# Croduino_SAMD_v1_0.net
KiCad netlist of a schematic drawn in EAGLE
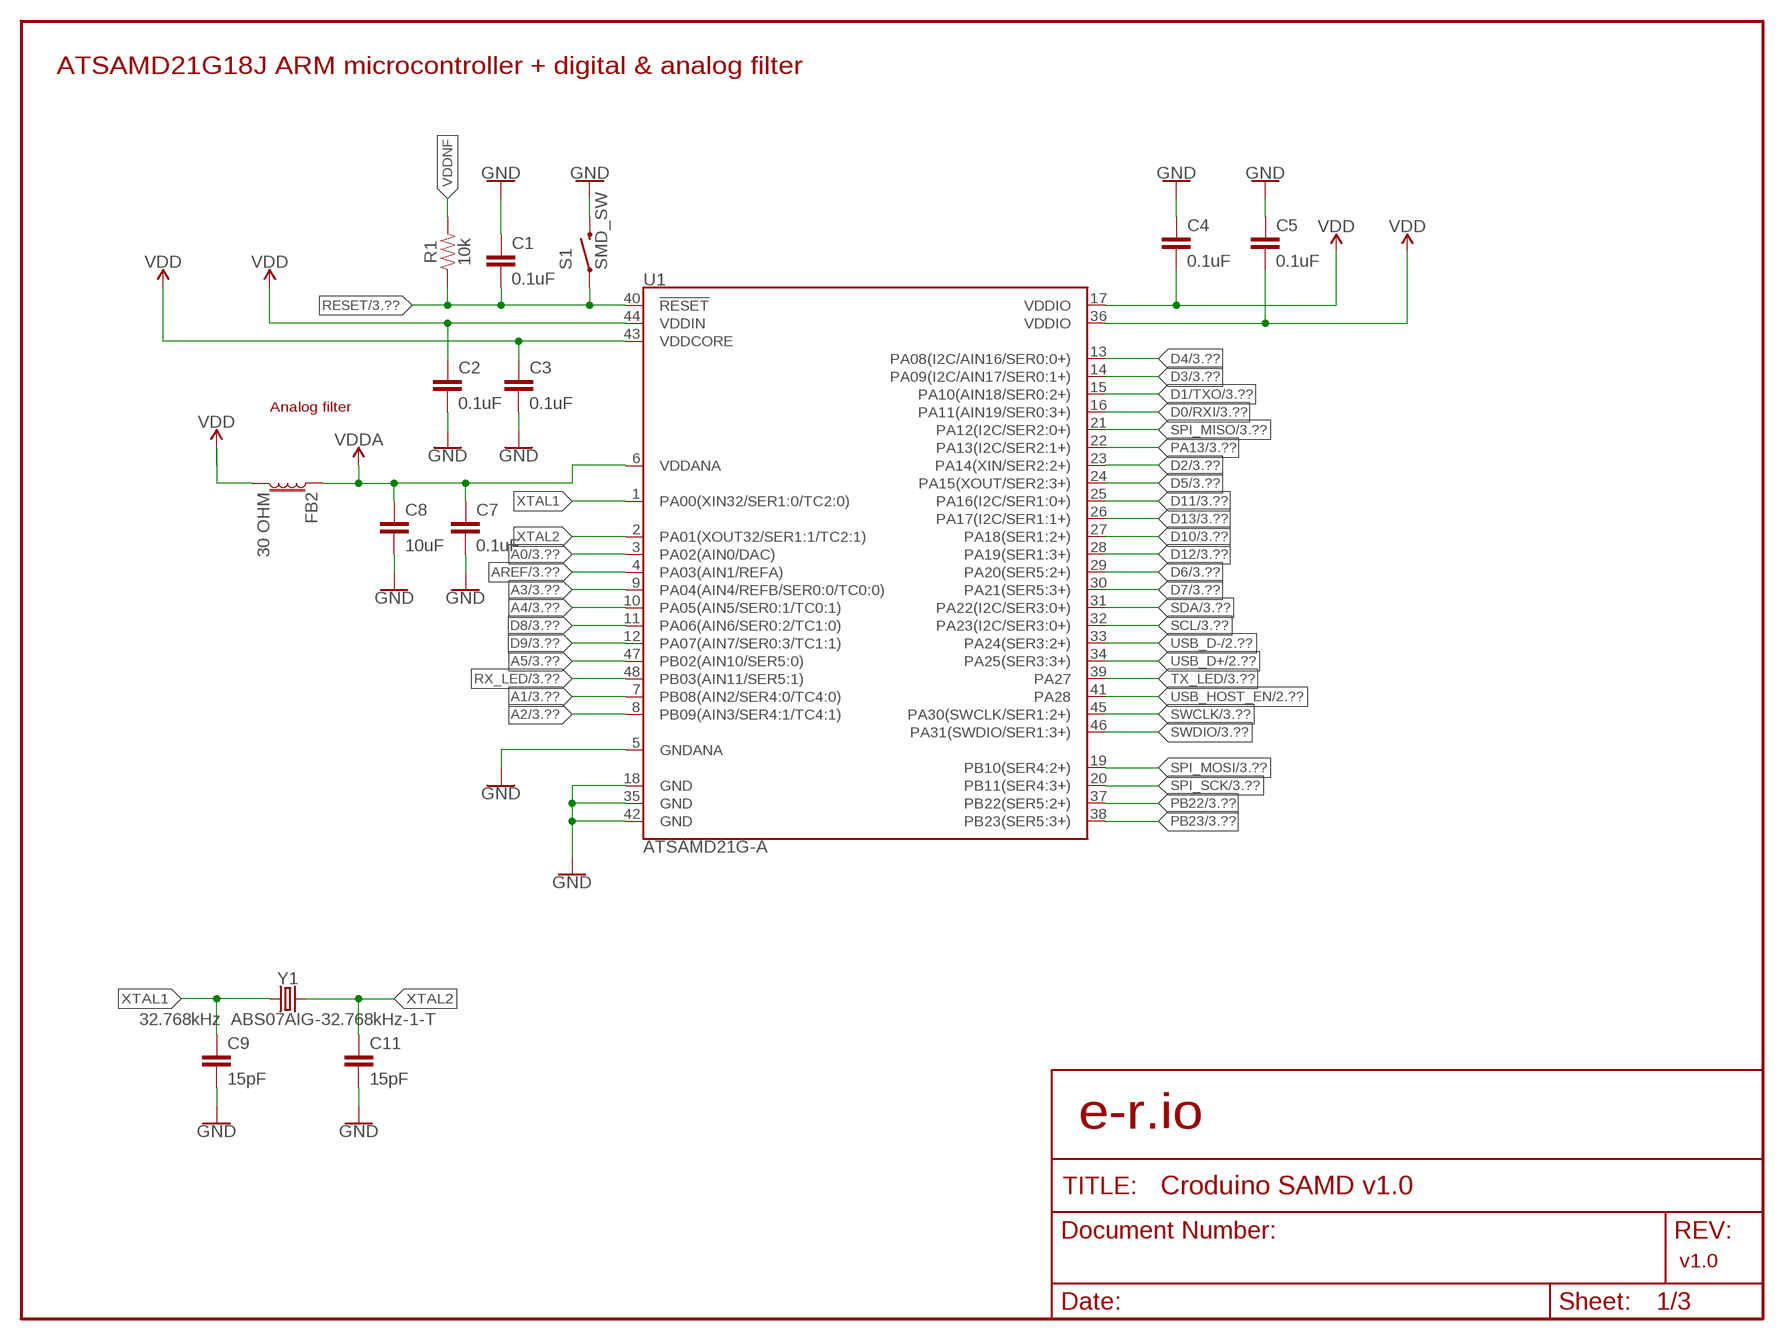
[diagram p0: schematic, sheet 1]
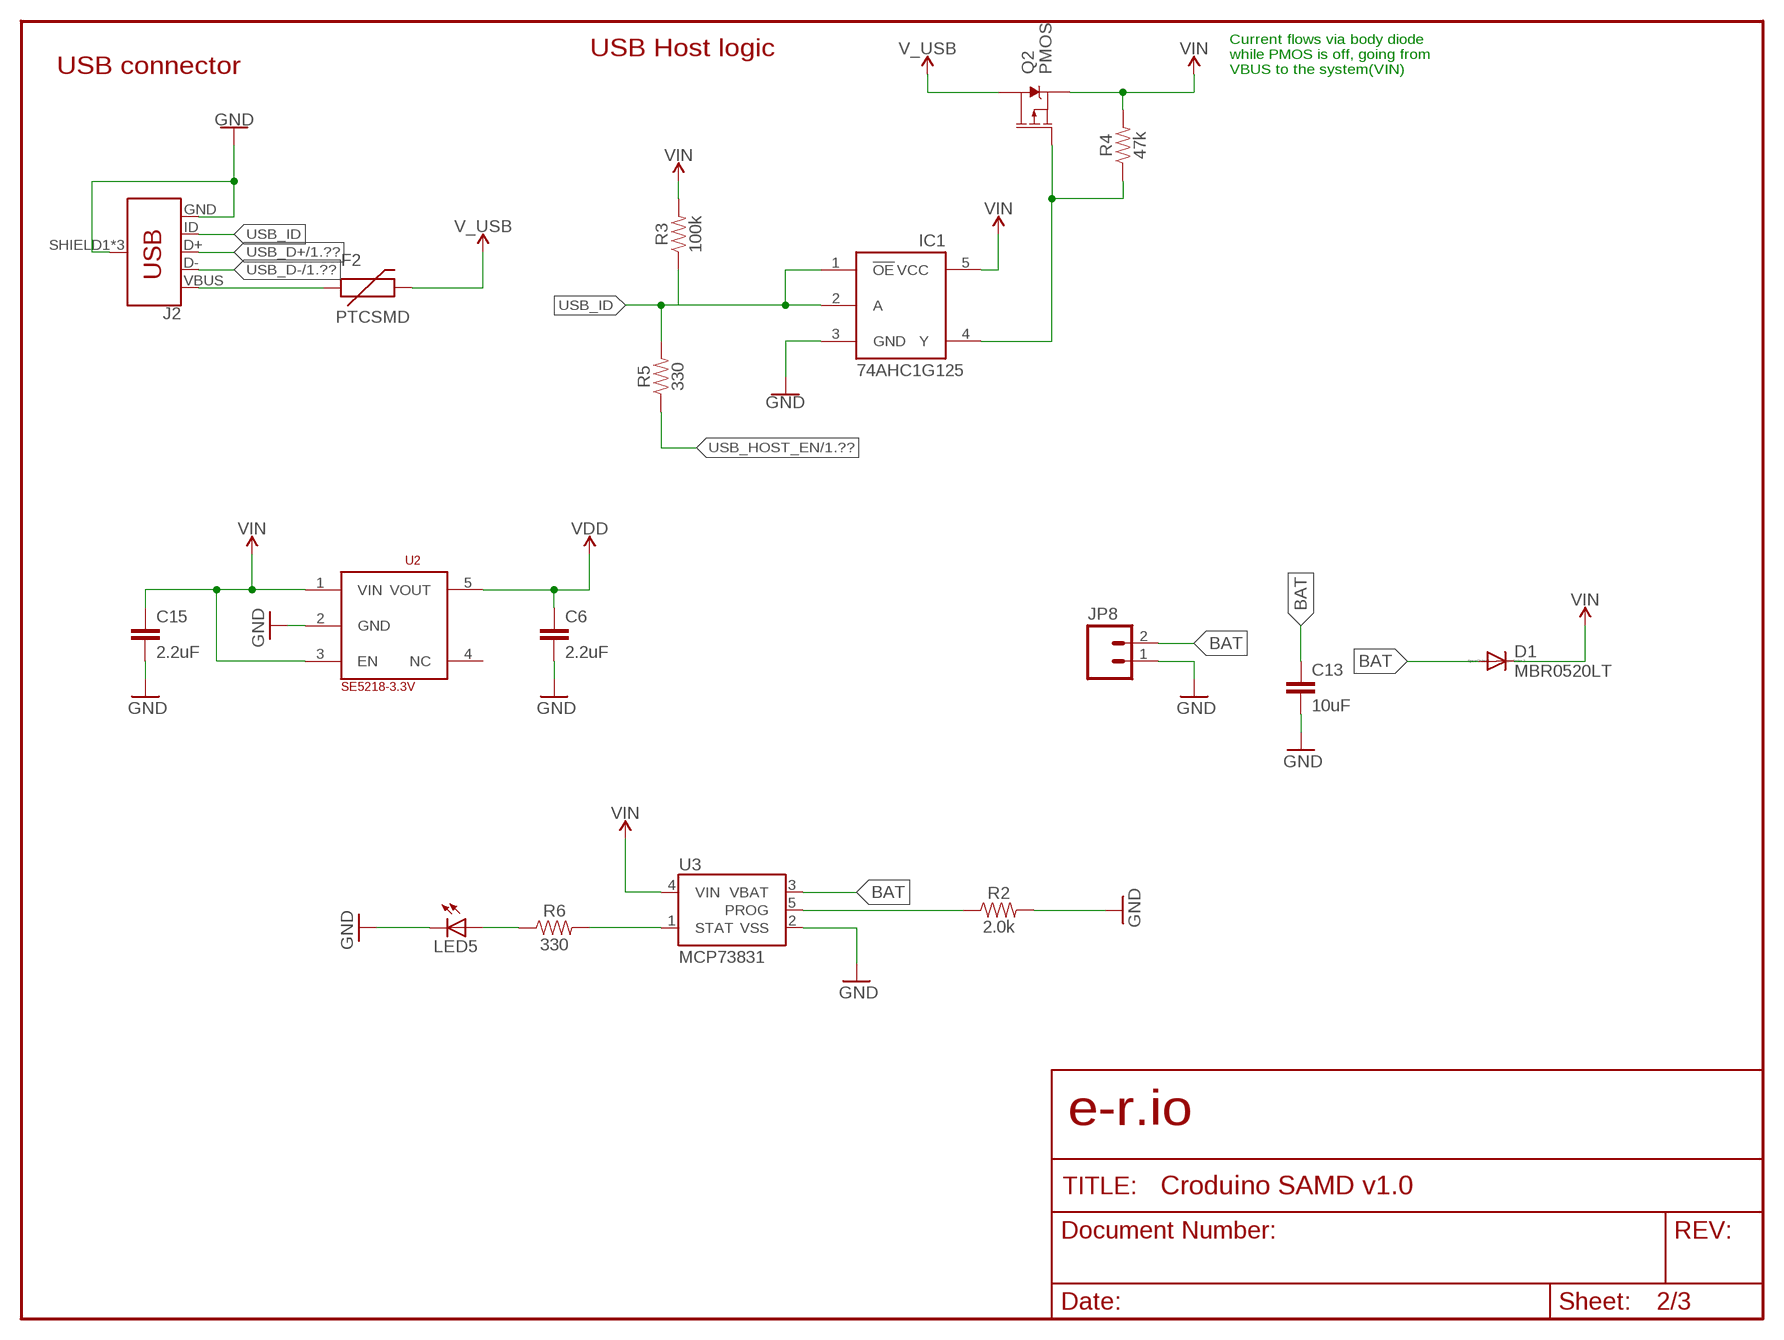
[diagram p1: schematic, sheet 2]
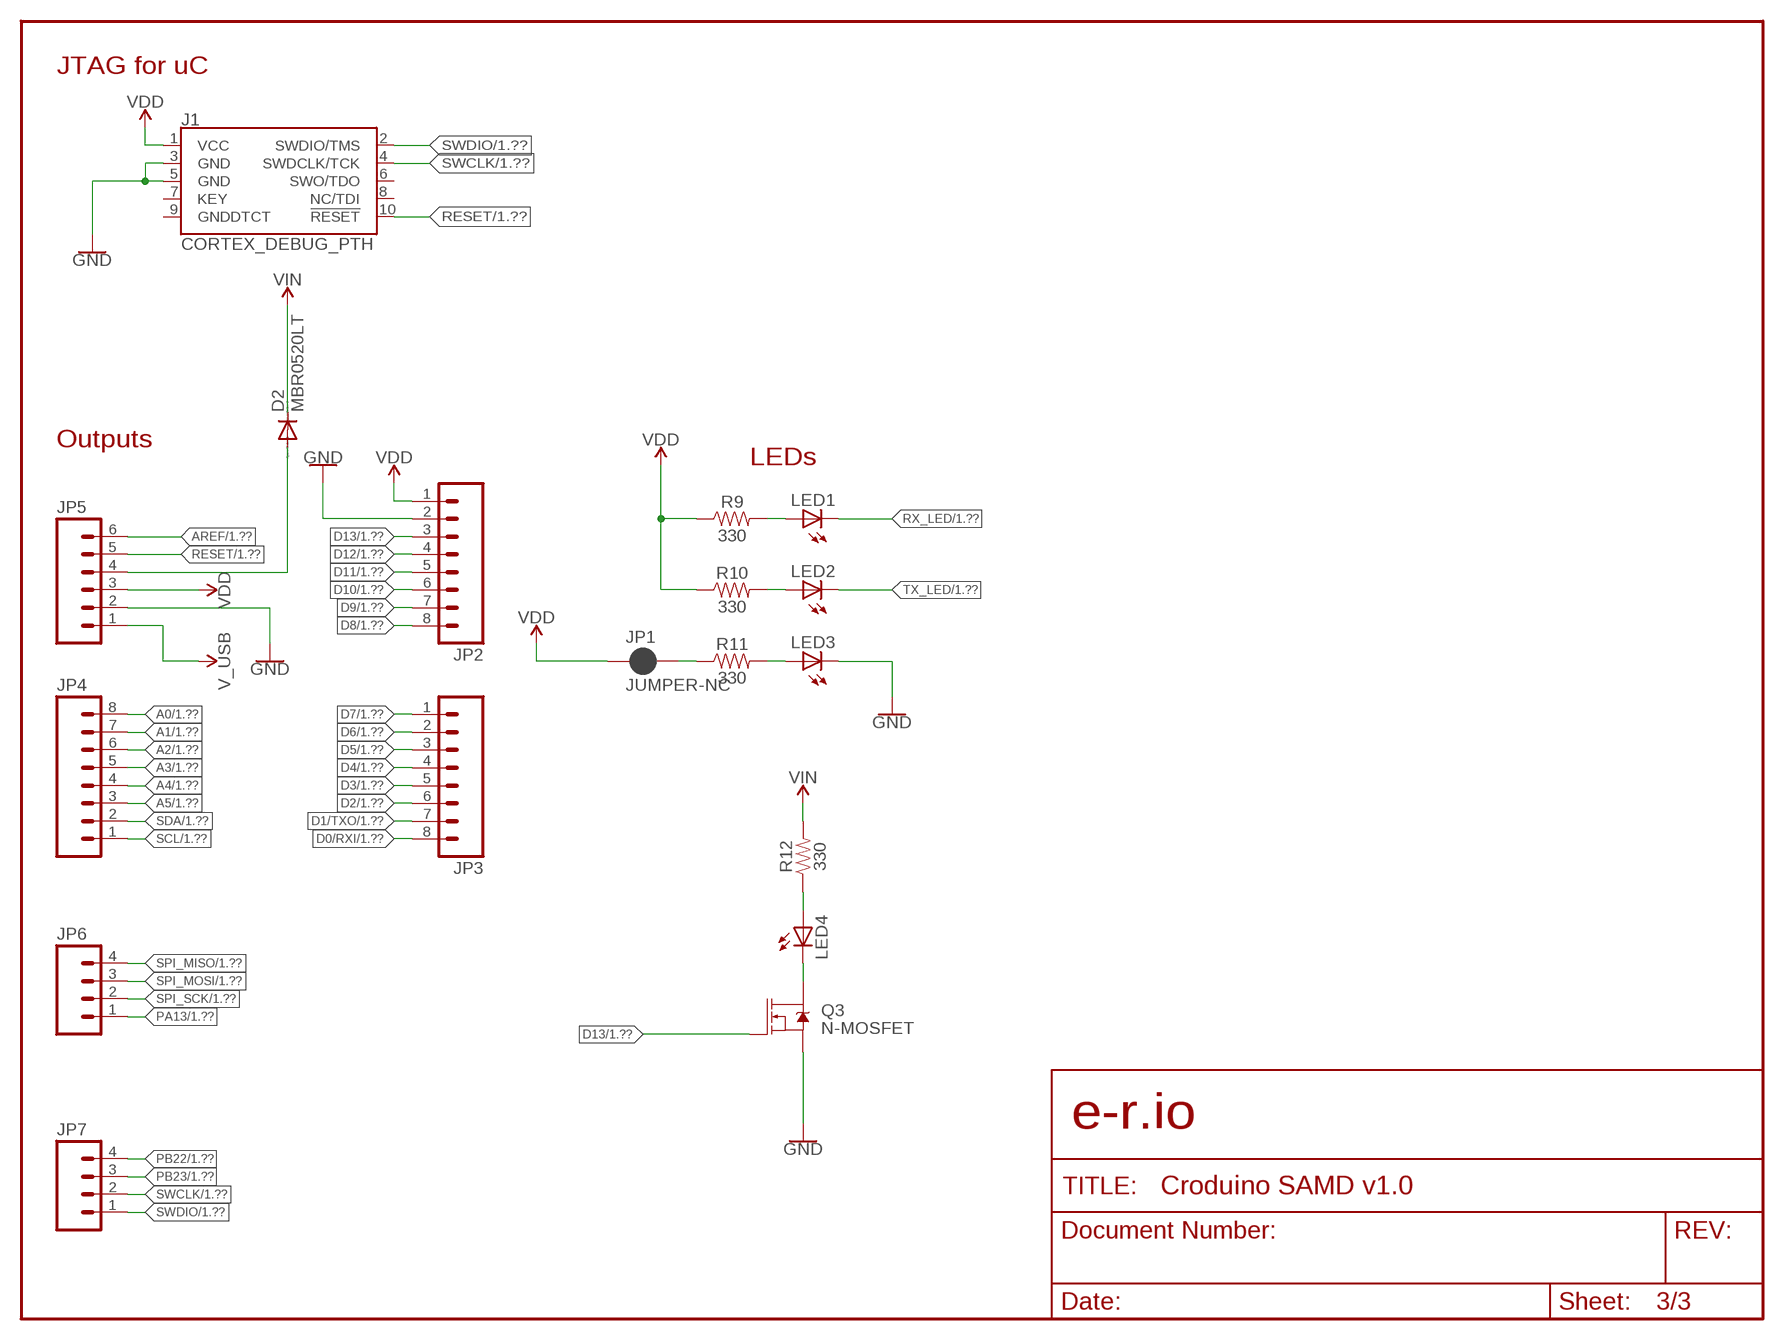
[diagram p2: schematic, sheet 3]

(export (version "E")
  (design (tool "Eeschema 10.0.6"))
  (components
    (comp (ref "C6")
      (value "2.2uF")
      (footprint "eagle-import:0603")
      (libsource (lib "eagle-import") (part "2.2UF-0603-10V-20%"))
    )
    (comp (ref "C13")
      (value "10uF")
      (footprint "eagle-import:1206")
      (libsource (lib "eagle-import") (part "10UF-1206-6.3V-20%"))
    )
    (comp (ref "C15")
      (value "2.2uF")
      (footprint "eagle-import:0603")
      (libsource (lib "eagle-import") (part "2.2UF-0603-10V-20%"))
    )
    (comp (ref "D1")
      (value "MBR0520LT")
      (footprint "eagle-import:SOD123")
      (libsource (lib "eagle-import") (part "MBR0520LT"))
    )
    (comp (ref "F2")
      (value "PTCSMD")
      (footprint "eagle-import:PTC-1206")
      (libsource (lib "eagle-import") (part "PTCSMD"))
    )
    (comp (ref "IC1")
      (value "74AHC1G125")
      (footprint "eagle-import:SOT23-5L")
      (libsource (lib "eagle-import") (part "74AHC1G125"))
    )
    (comp (ref "J2")
      (value "USB_MICRO-BREDUCED_PASTE")
      (footprint "eagle-import:USB-B-MICRO-SMD_RED_PASTE")
      (libsource (lib "eagle-import") (part "USB_MICRO-BREDUCED_PASTE"))
    )
    (comp (ref "JP8")
      (value "M02-JST-2MM-SMT")
      (footprint "eagle-import:JST-2-SMD")
      (libsource (lib "eagle-import") (part "M02-JST-2MM-SMT"))
    )
    (comp (ref "LED5")
      (value "LEDCHIPLED_0805")
      (footprint "eagle-import:CHIPLED_0805")
      (libsource (lib "eagle-import") (part "LEDCHIPLED_0805"))
    )
    (comp (ref "Q2")
      (value "PMOS")
      (footprint "eagle-import:SOT23-3")
      (libsource (lib "eagle-import") (part "MOSFET_PCH-DMG2307L"))
    )
    (comp (ref "R2")
      (value "2.0k")
      (footprint "eagle-import:0603")
      (libsource (lib "eagle-import") (part "2.0KOHM-0603-1/10W-5%"))
    )
    (comp (ref "R3")
      (value "100k")
      (footprint "eagle-import:0603")
      (libsource (lib "eagle-import") (part "100KOHM-0603-1/10W-1%"))
    )
    (comp (ref "R4")
      (value "47k")
      (footprint "eagle-import:0603")
      (libsource (lib "eagle-import") (part "47KOHM-0603-1/10W-1%"))
    )
    (comp (ref "R5")
      (value "330")
      (footprint "eagle-import:0603")
      (libsource (lib "eagle-import") (part "330OHM-0603-1/10W-1%"))
    )
    (comp (ref "R6")
      (value "330")
      (footprint "eagle-import:0603")
      (libsource (lib "eagle-import") (part "330OHM-0603-1/10W-1%"))
    )
    (comp (ref "U2")
      (value "SE5218-3.3V")
      (footprint "eagle-import:SOT23-5")
      (libsource (lib "eagle-import") (part "SE5218"))
    )
    (comp (ref "U3")
      (value "MCP73831")
      (footprint "eagle-import:SOT23-5")
      (libsource (lib "eagle-import") (part "MCP73831"))
    )
    (comp (ref "C1")
      (value "0.1uF")
      (footprint "eagle-import:0603")
      (libsource (lib "eagle-import") (part "0.1UF-0603-25V-(+80/-20%)"))
    )
    (comp (ref "C2")
      (value "0.1uF")
      (footprint "eagle-import:0603")
      (libsource (lib "eagle-import") (part "0.1UF-0603-25V-(+80/-20%)"))
    )
    (comp (ref "C3")
      (value "0.1uF")
      (footprint "eagle-import:0603")
      (libsource (lib "eagle-import") (part "0.1UF-0603-25V-(+80/-20%)"))
    )
    (comp (ref "C4")
      (value "0.1uF")
      (footprint "eagle-import:0603")
      (libsource (lib "eagle-import") (part "0.1UF-0603-25V-(+80/-20%)"))
    )
    (comp (ref "C5")
      (value "0.1uF")
      (footprint "eagle-import:0603")
      (libsource (lib "eagle-import") (part "0.1UF-0603-25V-(+80/-20%)"))
    )
    (comp (ref "C7")
      (value "0.1uF")
      (footprint "eagle-import:0603")
      (libsource (lib "eagle-import") (part "0.1UF-0603-25V-(+80/-20%)"))
    )
    (comp (ref "C8")
      (value "10uF")
      (footprint "eagle-import:1206")
      (libsource (lib "eagle-import") (part "10UF-1206-6.3V-20%"))
    )
    (comp (ref "C9")
      (value "15pF")
      (footprint "eagle-import:0603")
      (libsource (lib "eagle-import") (part "15PF-0603-50V-5%"))
    )
    (comp (ref "C11")
      (value "15pF")
      (footprint "eagle-import:0603")
      (libsource (lib "eagle-import") (part "15PF-0603-50V-5%"))
    )
    (comp (ref "FB2")
      (value "30 OHM")
      (footprint "eagle-import:0603")
      (libsource (lib "eagle-import") (part "FERRITE_BEAD-0603"))
    )
    (comp (ref "R1")
      (value "10k")
      (footprint "eagle-import:0603")
      (libsource (lib "eagle-import") (part "10KOHM-0603-1/10W-1%"))
    )
    (comp (ref "S1")
      (value "SMD_SW")
      (footprint "eagle-import:TACTILE_SWITCH_SMD")
      (libsource (lib "eagle-import") (part "SWITCH-MOMENTARY-2SMD"))
    )
    (comp (ref "U1")
      (value "ATSAMD21G-A")
      (footprint "eagle-import:TQFP-48")
      (libsource (lib "eagle-import") (part "ATSAMD21G-A"))
    )
    (comp (ref "Y1")
      (value "32.768kHz ABS07AIG-32.768kHz-1-T")
      (footprint "eagle-import:CRYSTAL-SMD-3.2X1.5MM")
      (libsource (lib "eagle-import") (part "CRYSTAL-32.768KHZSMD-3.2X1.5"))
    )
    (comp (ref "D2")
      (value "MBR0520LT")
      (footprint "eagle-import:SOD123")
      (libsource (lib "eagle-import") (part "MBR0520LT"))
    )
    (comp (ref "J1")
      (value "CORTEX_DEBUG_PTH")
      (footprint "eagle-import:2X5-PTH-1.27MM")
      (libsource (lib "eagle-import") (part "CORTEX_DEBUG_PTH"))
    )
    (comp (ref "JP1")
      (value "JUMPER-NC")
      (footprint "eagle-import:SMT-JUMPER_2_NC_PASTE_NO-SILK")
      (libsource (lib "eagle-import") (part "JUMPER-SMT_2_NC_PASTE_NO-SILK"))
    )
    (comp (ref "JP2")
      (value "M081X08")
      (footprint "eagle-import:1X08")
      (libsource (lib "eagle-import") (part "M081X08"))
    )
    (comp (ref "JP3")
      (value "M081X08")
      (footprint "eagle-import:1X08")
      (libsource (lib "eagle-import") (part "M081X08"))
    )
    (comp (ref "JP4")
      (value "M081X08")
      (footprint "eagle-import:1X08")
      (libsource (lib "eagle-import") (part "M081X08"))
    )
    (comp (ref "JP5")
      (value "M06SIP")
      (footprint "eagle-import:1X06")
      (libsource (lib "eagle-import") (part "M06SIP"))
    )
    (comp (ref "JP6")
      (value "M04PTH")
      (footprint "eagle-import:1X04")
      (libsource (lib "eagle-import") (part "M04PTH"))
    )
    (comp (ref "JP7")
      (value "M04PTH")
      (footprint "eagle-import:1X04")
      (libsource (lib "eagle-import") (part "M04PTH"))
    )
    (comp (ref "LED1")
      (value "LEDCHIPLED_0805")
      (footprint "eagle-import:CHIPLED_0805")
      (libsource (lib "eagle-import") (part "LEDCHIPLED_0805"))
    )
    (comp (ref "LED2")
      (value "LEDCHIPLED_0805")
      (footprint "eagle-import:CHIPLED_0805")
      (libsource (lib "eagle-import") (part "LEDCHIPLED_0805"))
    )
    (comp (ref "LED3")
      (value "LEDCHIPLED_0805")
      (footprint "eagle-import:CHIPLED_0805")
      (libsource (lib "eagle-import") (part "LEDCHIPLED_0805"))
    )
    (comp (ref "LED4")
      (value "LEDCHIPLED_0805")
      (footprint "eagle-import:CHIPLED_0805")
      (libsource (lib "eagle-import") (part "LEDCHIPLED_0805"))
    )
    (comp (ref "Q3")
      (value "N-MOSFET")
      (footprint "eagle-import:SOT23-3")
      (libsource (lib "eagle-import") (part "MOSFET-NCH-AO3404A"))
    )
    (comp (ref "R9")
      (value "330")
      (footprint "eagle-import:0603")
      (libsource (lib "eagle-import") (part "330OHM-0603-1/10W-1%"))
    )
    (comp (ref "R10")
      (value "330")
      (footprint "eagle-import:0603")
      (libsource (lib "eagle-import") (part "330OHM-0603-1/10W-1%"))
    )
    (comp (ref "R11")
      (value "330")
      (footprint "eagle-import:0603")
      (libsource (lib "eagle-import") (part "330OHM-0603-1/10W-1%"))
    )
    (comp (ref "R12")
      (value "330")
      (footprint "eagle-import:0603")
      (libsource (lib "eagle-import") (part "330OHM-0603-1/10W-1%"))
    )
  )
  (nets
    (net (code "1") (name "A0") (class "Default")
      (node (ref "JP4") (pin "8") (pinfunction "8_8") (pintype "passive"))
      (node (ref "U1") (pin "3") (pinfunction "PA02(AIN0/DAC)_3") (pintype "bidirectional"))
    )
    (net (code "2") (name "A1") (class "Default")
      (node (ref "JP4") (pin "7") (pinfunction "7_7") (pintype "passive"))
      (node (ref "U1") (pin "7") (pinfunction "PB08(AIN2/SER4:0/TC4:0)_7") (pintype "bidirectional"))
    )
    (net (code "3") (name "A2") (class "Default")
      (node (ref "JP4") (pin "6") (pinfunction "6_6") (pintype "passive"))
      (node (ref "U1") (pin "8") (pinfunction "PB09(AIN3/SER4:1/TC4:1)_8") (pintype "bidirectional"))
    )
    (net (code "4") (name "A3") (class "Default")
      (node (ref "JP4") (pin "5") (pinfunction "5_5") (pintype "passive"))
      (node (ref "U1") (pin "9") (pinfunction "PA04(AIN4/REFB/SER0:0/TC0:0)_9") (pintype "bidirectional"))
    )
    (net (code "5") (name "A4") (class "Default")
      (node (ref "JP4") (pin "4") (pinfunction "4_4") (pintype "passive"))
      (node (ref "U1") (pin "10") (pinfunction "PA05(AIN5/SER0:1/TC0:1)_10") (pintype "bidirectional"))
    )
    (net (code "6") (name "A5") (class "Default")
      (node (ref "JP4") (pin "3") (pinfunction "3_3") (pintype "passive"))
      (node (ref "U1") (pin "47") (pinfunction "PB02(AIN10/SER5:0)_47") (pintype "bidirectional"))
    )
    (net (code "7") (name "AREF") (class "Default")
      (node (ref "JP5") (pin "6") (pinfunction "6_6") (pintype "passive"))
      (node (ref "U1") (pin "4") (pinfunction "PA03(AIN1/REFA)_4") (pintype "bidirectional"))
    )
    (net (code "8") (name "BAT") (class "Default")
      (node (ref "C13") (pin "1") (pinfunction "1_1") (pintype "passive"))
      (node (ref "D1") (pin "A") (pinfunction "A_A") (pintype "passive"))
      (node (ref "JP8") (pin "2") (pinfunction "2_2") (pintype "passive"))
      (node (ref "U3") (pin "3") (pinfunction "VBAT_3") (pintype "power_in"))
    )
    (net (code "9") (name "D0{slash}RXI") (class "Default")
      (node (ref "JP3") (pin "8") (pinfunction "8_8") (pintype "passive"))
      (node (ref "U1") (pin "16") (pinfunction "PA11(AIN19/SER0:3+)_16") (pintype "bidirectional"))
    )
    (net (code "10") (name "D1{slash}TXO") (class "Default")
      (node (ref "JP3") (pin "7") (pinfunction "7_7") (pintype "passive"))
      (node (ref "U1") (pin "15") (pinfunction "PA10(AIN18/SER0:2+)_15") (pintype "bidirectional"))
    )
    (net (code "11") (name "D2") (class "Default")
      (node (ref "JP3") (pin "6") (pinfunction "6_6") (pintype "passive"))
      (node (ref "U1") (pin "23") (pinfunction "PA14(XIN/SER2:2+)_23") (pintype "bidirectional"))
    )
    (net (code "12") (name "D3") (class "Default")
      (node (ref "JP3") (pin "5") (pinfunction "5_5") (pintype "passive"))
      (node (ref "U1") (pin "14") (pinfunction "PA09(I2C/AIN17/SER0:1+)_14") (pintype "bidirectional"))
    )
    (net (code "13") (name "D4") (class "Default")
      (node (ref "JP3") (pin "4") (pinfunction "4_4") (pintype "passive"))
      (node (ref "U1") (pin "13") (pinfunction "PA08(I2C/AIN16/SER0:0+)_13") (pintype "bidirectional"))
    )
    (net (code "14") (name "D5") (class "Default")
      (node (ref "JP3") (pin "3") (pinfunction "3_3") (pintype "passive"))
      (node (ref "U1") (pin "24") (pinfunction "PA15(XOUT/SER2:3+)_24") (pintype "bidirectional"))
    )
    (net (code "15") (name "D6") (class "Default")
      (node (ref "JP3") (pin "2") (pinfunction "2_2") (pintype "passive"))
      (node (ref "U1") (pin "29") (pinfunction "PA20(SER5:2+)_29") (pintype "bidirectional"))
    )
    (net (code "16") (name "D7") (class "Default")
      (node (ref "JP3") (pin "1") (pinfunction "1_1") (pintype "passive"))
      (node (ref "U1") (pin "30") (pinfunction "PA21(SER5:3+)_30") (pintype "bidirectional"))
    )
    (net (code "17") (name "D8") (class "Default")
      (node (ref "JP2") (pin "8") (pinfunction "8_8") (pintype "passive"))
      (node (ref "U1") (pin "11") (pinfunction "PA06(AIN6/SER0:2/TC1:0)_11") (pintype "bidirectional"))
    )
    (net (code "18") (name "D9") (class "Default")
      (node (ref "JP2") (pin "7") (pinfunction "7_7") (pintype "passive"))
      (node (ref "U1") (pin "12") (pinfunction "PA07(AIN7/SER0:3/TC1:1)_12") (pintype "bidirectional"))
    )
    (net (code "19") (name "D10") (class "Default")
      (node (ref "JP2") (pin "6") (pinfunction "6_6") (pintype "passive"))
      (node (ref "U1") (pin "27") (pinfunction "PA18(SER1:2+)_27") (pintype "bidirectional"))
    )
    (net (code "20") (name "D11") (class "Default")
      (node (ref "JP2") (pin "5") (pinfunction "5_5") (pintype "passive"))
      (node (ref "U1") (pin "25") (pinfunction "PA16(I2C/SER1:0+)_25") (pintype "bidirectional"))
    )
    (net (code "21") (name "D12") (class "Default")
      (node (ref "JP2") (pin "4") (pinfunction "4_4") (pintype "passive"))
      (node (ref "U1") (pin "28") (pinfunction "PA19(SER1:3+)_28") (pintype "bidirectional"))
    )
    (net (code "22") (name "D13") (class "Default")
      (node (ref "JP2") (pin "3") (pinfunction "3_3") (pintype "passive"))
      (node (ref "Q3") (pin "1") (pinfunction "G_1") (pintype "bidirectional"))
      (node (ref "U1") (pin "26") (pinfunction "PA17(I2C/SER1:1+)_26") (pintype "bidirectional"))
    )
    (net (code "23") (name "GND") (class "Default")
      (node (ref "C1") (pin "1") (pinfunction "1_1") (pintype "passive"))
      (node (ref "C11") (pin "2") (pinfunction "2_2") (pintype "passive"))
      (node (ref "C13") (pin "2") (pinfunction "2_2") (pintype "passive"))
      (node (ref "C15") (pin "2") (pinfunction "2_2") (pintype "passive"))
      (node (ref "C2") (pin "2") (pinfunction "2_2") (pintype "passive"))
      (node (ref "C3") (pin "2") (pinfunction "2_2") (pintype "passive"))
      (node (ref "C4") (pin "1") (pinfunction "1_1") (pintype "passive"))
      (node (ref "C5") (pin "1") (pinfunction "1_1") (pintype "passive"))
      (node (ref "C6") (pin "2") (pinfunction "2_2") (pintype "passive"))
      (node (ref "C7") (pin "2") (pinfunction "2_2") (pintype "passive"))
      (node (ref "C8") (pin "2") (pinfunction "2_2") (pintype "passive"))
      (node (ref "C9") (pin "2") (pinfunction "2_2") (pintype "passive"))
      (node (ref "IC1") (pin "3") (pinfunction "GND_3") (pintype "power_in"))
      (node (ref "J1") (pin "3") (pinfunction "GND_3") (pintype "bidirectional"))
      (node (ref "J1") (pin "5") (pinfunction "GND_5") (pintype "bidirectional"))
      (node (ref "J2") (pin "GND") (pinfunction "GND_GND") (pintype "power_in"))
      (node (ref "J2") (pin "SHIELD1") (pinfunction "SHIELD_SHIELD1") (pintype "bidirectional"))
      (node (ref "J2") (pin "SHIELD2") (pinfunction "SHIELD_SHIELD2") (pintype "bidirectional"))
      (node (ref "J2") (pin "SHIELD3") (pinfunction "SHIELD_SHIELD3") (pintype "bidirectional"))
      (node (ref "JP2") (pin "2") (pinfunction "2_2") (pintype "passive"))
      (node (ref "JP5") (pin "2") (pinfunction "2_2") (pintype "passive"))
      (node (ref "JP8") (pin "1") (pinfunction "1_1") (pintype "passive"))
      (node (ref "LED3") (pin "C") (pinfunction "C_C") (pintype "passive"))
      (node (ref "LED5") (pin "C") (pinfunction "C_C") (pintype "passive"))
      (node (ref "Q3") (pin "2") (pinfunction "S_2") (pintype "bidirectional"))
      (node (ref "R2") (pin "2") (pinfunction "2_2") (pintype "passive"))
      (node (ref "S1") (pin "3") (pinfunction "2_3") (pintype "passive"))
      (node (ref "U1") (pin "18") (pinfunction "GND_18") (pintype "bidirectional"))
      (node (ref "U1") (pin "35") (pinfunction "GND_35") (pintype "bidirectional"))
      (node (ref "U1") (pin "42") (pinfunction "GND_42") (pintype "bidirectional"))
      (node (ref "U1") (pin "5") (pinfunction "GNDANA_5") (pintype "bidirectional"))
      (node (ref "U2") (pin "2") (pinfunction "GND_2") (pintype "bidirectional"))
      (node (ref "U3") (pin "2") (pinfunction "VSS_2") (pintype "power_in"))
    )
    (net (code "24") (name "Net-(D2-PadA)") (class "Default")
      (node (ref "D2") (pin "A") (pinfunction "A_A") (pintype "passive"))
      (node (ref "JP5") (pin "4") (pinfunction "4_4") (pintype "passive"))
    )
    (net (code "25") (name "Net-(F2-Pad1)") (class "Default")
      (node (ref "F2") (pin "1") (pinfunction "1_1") (pintype "bidirectional"))
      (node (ref "J2") (pin "VBUS") (pinfunction "VBUS_VBUS") (pintype "power_in"))
    )
    (net (code "26") (name "Net-(IC1-Y)") (class "Default")
      (node (ref "IC1") (pin "4") (pinfunction "Y_4") (pintype "output"))
      (node (ref "Q2") (pin "1") (pinfunction "G_1") (pintype "bidirectional"))
      (node (ref "R4") (pin "1") (pinfunction "1_1") (pintype "passive"))
    )
    (net (code "27") (name "Net-(JP1-Pad2)") (class "Default")
      (node (ref "JP1") (pin "2") (pinfunction "2_2") (pintype "passive"))
      (node (ref "R11") (pin "1") (pinfunction "1_1") (pintype "passive"))
    )
    (net (code "28") (name "Net-(LED1-PadA)") (class "Default")
      (node (ref "LED1") (pin "A") (pinfunction "A_A") (pintype "passive"))
      (node (ref "R9") (pin "2") (pinfunction "2_2") (pintype "passive"))
    )
    (net (code "29") (name "Net-(LED2-PadA)") (class "Default")
      (node (ref "LED2") (pin "A") (pinfunction "A_A") (pintype "passive"))
      (node (ref "R10") (pin "2") (pinfunction "2_2") (pintype "passive"))
    )
    (net (code "30") (name "Net-(LED3-PadA)") (class "Default")
      (node (ref "LED3") (pin "A") (pinfunction "A_A") (pintype "passive"))
      (node (ref "R11") (pin "2") (pinfunction "2_2") (pintype "passive"))
    )
    (net (code "31") (name "Net-(LED4-PadA)") (class "Default")
      (node (ref "LED4") (pin "A") (pinfunction "A_A") (pintype "passive"))
      (node (ref "R12") (pin "1") (pinfunction "1_1") (pintype "passive"))
    )
    (net (code "32") (name "Net-(LED5-PadA)") (class "Default")
      (node (ref "LED5") (pin "A") (pinfunction "A_A") (pintype "passive"))
      (node (ref "R6") (pin "1") (pinfunction "1_1") (pintype "passive"))
    )
    (net (code "33") (name "Net-(Q3-D)") (class "Default")
      (node (ref "LED4") (pin "C") (pinfunction "C_C") (pintype "passive"))
      (node (ref "Q3") (pin "3") (pinfunction "D_3") (pintype "bidirectional"))
    )
    (net (code "34") (name "Net-(U3-PROG)") (class "Default")
      (node (ref "R2") (pin "1") (pinfunction "1_1") (pintype "passive"))
      (node (ref "U3") (pin "5") (pinfunction "PROG_5") (pintype "input"))
    )
    (net (code "35") (name "Net-(U3-STAT)") (class "Default")
      (node (ref "R6") (pin "2") (pinfunction "2_2") (pintype "passive"))
      (node (ref "U3") (pin "1") (pinfunction "STAT_1") (pintype "output"))
    )
    (net (code "36") (name "PA13") (class "Default")
      (node (ref "JP6") (pin "1") (pinfunction "1_1") (pintype "passive"))
      (node (ref "U1") (pin "22") (pinfunction "PA13(I2C/SER2:1+)_22") (pintype "bidirectional"))
    )
    (net (code "37") (name "PB22") (class "Default")
      (node (ref "JP7") (pin "4") (pinfunction "4_4") (pintype "passive"))
      (node (ref "U1") (pin "37") (pinfunction "PB22(SER5:2+)_37") (pintype "bidirectional"))
    )
    (net (code "38") (name "PB23") (class "Default")
      (node (ref "JP7") (pin "3") (pinfunction "3_3") (pintype "passive"))
      (node (ref "U1") (pin "38") (pinfunction "PB23(SER5:3+)_38") (pintype "bidirectional"))
    )
    (net (code "39") (name "RESET") (class "Default")
      (node (ref "C1") (pin "2") (pinfunction "2_2") (pintype "passive"))
      (node (ref "J1") (pin "10") (pinfunction "~{RESET}_10") (pintype "bidirectional"))
      (node (ref "JP5") (pin "5") (pinfunction "5_5") (pintype "passive"))
      (node (ref "R1") (pin "1") (pinfunction "1_1") (pintype "passive"))
      (node (ref "S1") (pin "1") (pinfunction "1_1") (pintype "passive"))
      (node (ref "U1") (pin "40") (pinfunction "~{RESET}_40") (pintype "bidirectional"))
    )
    (net (code "40") (name "RX_LED") (class "Default")
      (node (ref "LED1") (pin "C") (pinfunction "C_C") (pintype "passive"))
      (node (ref "U1") (pin "48") (pinfunction "PB03(AIN11/SER5:1)_48") (pintype "bidirectional"))
    )
    (net (code "41") (name "SCL") (class "Default")
      (node (ref "JP4") (pin "1") (pinfunction "1_1") (pintype "passive"))
      (node (ref "U1") (pin "32") (pinfunction "PA23(I2C/SER3:0+)_32") (pintype "bidirectional"))
    )
    (net (code "42") (name "SDA") (class "Default")
      (node (ref "JP4") (pin "2") (pinfunction "2_2") (pintype "passive"))
      (node (ref "U1") (pin "31") (pinfunction "PA22(I2C/SER3:0+)_31") (pintype "bidirectional"))
    )
    (net (code "43") (name "SPI_MISO") (class "Default")
      (node (ref "JP6") (pin "4") (pinfunction "4_4") (pintype "passive"))
      (node (ref "U1") (pin "21") (pinfunction "PA12(I2C/SER2:0+)_21") (pintype "bidirectional"))
    )
    (net (code "44") (name "SPI_MOSI") (class "Default")
      (node (ref "JP6") (pin "3") (pinfunction "3_3") (pintype "passive"))
      (node (ref "U1") (pin "19") (pinfunction "PB10(SER4:2+)_19") (pintype "bidirectional"))
    )
    (net (code "45") (name "SPI_SCK") (class "Default")
      (node (ref "JP6") (pin "2") (pinfunction "2_2") (pintype "passive"))
      (node (ref "U1") (pin "20") (pinfunction "PB11(SER4:3+)_20") (pintype "bidirectional"))
    )
    (net (code "46") (name "SWCLK") (class "Default")
      (node (ref "J1") (pin "4") (pinfunction "SWDCLK/TCK_4") (pintype "bidirectional"))
      (node (ref "JP7") (pin "2") (pinfunction "2_2") (pintype "passive"))
      (node (ref "U1") (pin "45") (pinfunction "PA30(SWCLK/SER1:2+)_45") (pintype "bidirectional"))
    )
    (net (code "47") (name "SWDIO") (class "Default")
      (node (ref "J1") (pin "2") (pinfunction "SWDIO/TMS_2") (pintype "bidirectional"))
      (node (ref "JP7") (pin "1") (pinfunction "1_1") (pintype "passive"))
      (node (ref "U1") (pin "46") (pinfunction "PA31(SWDIO/SER1:3+)_46") (pintype "bidirectional"))
    )
    (net (code "48") (name "TX_LED") (class "Default")
      (node (ref "LED2") (pin "C") (pinfunction "C_C") (pintype "passive"))
      (node (ref "U1") (pin "39") (pinfunction "PA27_39") (pintype "bidirectional"))
    )
    (net (code "49") (name "USB_D+") (class "Default")
      (node (ref "J2") (pin "D+") (pinfunction "D+_D+") (pintype "bidirectional"))
      (node (ref "U1") (pin "34") (pinfunction "PA25(SER3:3+)_34") (pintype "bidirectional"))
    )
    (net (code "50") (name "USB_D-") (class "Default")
      (node (ref "J2") (pin "D-") (pinfunction "D-_D-") (pintype "bidirectional"))
      (node (ref "U1") (pin "33") (pinfunction "PA24(SER3:2+)_33") (pintype "bidirectional"))
    )
    (net (code "51") (name "USB_HOST_EN") (class "Default")
      (node (ref "R5") (pin "1") (pinfunction "1_1") (pintype "passive"))
      (node (ref "U1") (pin "41") (pinfunction "PA28_41") (pintype "bidirectional"))
    )
    (net (code "52") (name "USB_ID") (class "Default")
      (node (ref "IC1") (pin "1") (pinfunction "~{OE}_1") (pintype "input"))
      (node (ref "IC1") (pin "2") (pinfunction "A_2") (pintype "input"))
      (node (ref "J2") (pin "ID") (pinfunction "ID_ID") (pintype "bidirectional"))
      (node (ref "R3") (pin "1") (pinfunction "1_1") (pintype "passive"))
      (node (ref "R5") (pin "2") (pinfunction "2_2") (pintype "passive"))
    )
    (net (code "53") (name "VDD") (class "Default")
      (node (ref "C2") (pin "1") (pinfunction "1_1") (pintype "passive"))
      (node (ref "C3") (pin "1") (pinfunction "1_1") (pintype "passive"))
      (node (ref "C4") (pin "2") (pinfunction "2_2") (pintype "passive"))
      (node (ref "C5") (pin "2") (pinfunction "2_2") (pintype "passive"))
      (node (ref "C6") (pin "1") (pinfunction "1_1") (pintype "passive"))
      (node (ref "FB2") (pin "2") (pinfunction "2_2") (pintype "passive"))
      (node (ref "J1") (pin "1") (pinfunction "VCC_1") (pintype "bidirectional"))
      (node (ref "JP1") (pin "1") (pinfunction "1_1") (pintype "passive"))
      (node (ref "JP2") (pin "1") (pinfunction "1_1") (pintype "passive"))
      (node (ref "JP5") (pin "3") (pinfunction "3_3") (pintype "passive"))
      (node (ref "R10") (pin "1") (pinfunction "1_1") (pintype "passive"))
      (node (ref "R9") (pin "1") (pinfunction "1_1") (pintype "passive"))
      (node (ref "U1") (pin "17") (pinfunction "VDDIO_17") (pintype "bidirectional"))
      (node (ref "U1") (pin "36") (pinfunction "VDDIO_36") (pintype "bidirectional"))
      (node (ref "U1") (pin "43") (pinfunction "VDDCORE_43") (pintype "bidirectional"))
      (node (ref "U1") (pin "44") (pinfunction "VDDIN_44") (pintype "bidirectional"))
      (node (ref "U2") (pin "5") (pinfunction "VOUT_5") (pintype "bidirectional"))
    )
    (net (code "54") (name "VDDA") (class "Default")
      (node (ref "C7") (pin "1") (pinfunction "1_1") (pintype "passive"))
      (node (ref "C8") (pin "1") (pinfunction "1_1") (pintype "passive"))
      (node (ref "FB2") (pin "1") (pinfunction "1_1") (pintype "passive"))
      (node (ref "U1") (pin "6") (pinfunction "VDDANA_6") (pintype "bidirectional"))
    )
    (net (code "55") (name "VDDNF") (class "Default")
      (node (ref "R1") (pin "2") (pinfunction "2_2") (pintype "passive"))
    )
    (net (code "56") (name "VIN") (class "Default")
      (node (ref "C15") (pin "1") (pinfunction "1_1") (pintype "passive"))
      (node (ref "D1") (pin "C") (pinfunction "C_C") (pintype "passive"))
      (node (ref "D2") (pin "C") (pinfunction "C_C") (pintype "passive"))
      (node (ref "IC1") (pin "5") (pinfunction "VCC_5") (pintype "power_in"))
      (node (ref "Q2") (pin "2") (pinfunction "S_2") (pintype "bidirectional"))
      (node (ref "R12") (pin "2") (pinfunction "2_2") (pintype "passive"))
      (node (ref "R3") (pin "2") (pinfunction "2_2") (pintype "passive"))
      (node (ref "R4") (pin "2") (pinfunction "2_2") (pintype "passive"))
      (node (ref "U2") (pin "1") (pinfunction "VIN_1") (pintype "bidirectional"))
      (node (ref "U2") (pin "3") (pinfunction "EN_3") (pintype "bidirectional"))
      (node (ref "U3") (pin "4") (pinfunction "VIN_4") (pintype "power_in"))
    )
    (net (code "57") (name "V_USB") (class "Default")
      (node (ref "F2") (pin "2") (pinfunction "2_2") (pintype "bidirectional"))
      (node (ref "JP5") (pin "1") (pinfunction "1_1") (pintype "passive"))
      (node (ref "Q2") (pin "3") (pinfunction "D_3") (pintype "bidirectional"))
    )
    (net (code "58") (name "XTAL1") (class "Default")
      (node (ref "C9") (pin "1") (pinfunction "1_1") (pintype "passive"))
      (node (ref "U1") (pin "1") (pinfunction "PA00(XIN32/SER1:0/TC2:0)_1") (pintype "bidirectional"))
      (node (ref "Y1") (pin "P$1") (pinfunction "1_P$1") (pintype "passive"))
    )
    (net (code "59") (name "XTAL2") (class "Default")
      (node (ref "C11") (pin "1") (pinfunction "1_1") (pintype "passive"))
      (node (ref "U1") (pin "2") (pinfunction "PA01(XOUT32/SER1:1/TC2:1)_2") (pintype "bidirectional"))
      (node (ref "Y1") (pin "P$2") (pinfunction "2_P$2") (pintype "passive"))
    )
    (net (code "60") (name "unconnected-(J1-GNDDTCT-Pad9)") (class "Default")
      (node (ref "J1") (pin "9") (pinfunction "GNDDTCT_9") (pintype "bidirectional"))
    )
    (net (code "61") (name "unconnected-(J1-KEY-Pad7)") (class "Default")
      (node (ref "J1") (pin "7") (pinfunction "KEY_7") (pintype "bidirectional"))
    )
    (net (code "62") (name "unconnected-(J1-NC{slash}TDI-Pad8)") (class "Default")
      (node (ref "J1") (pin "8") (pinfunction "NC/TDI_8") (pintype "bidirectional"))
    )
    (net (code "63") (name "unconnected-(J1-SWO{slash}TDO-Pad6)") (class "Default")
      (node (ref "J1") (pin "6") (pinfunction "SWO/TDO_6") (pintype "bidirectional"))
    )
    (net (code "64") (name "unconnected-(U2-NC-Pad4)") (class "Default")
      (node (ref "U2") (pin "4") (pinfunction "NC_4") (pintype "bidirectional"))
    )
  )
)
